# Power_Regulation.net
KiCad netlist of a schematic drawn in Altium Designer
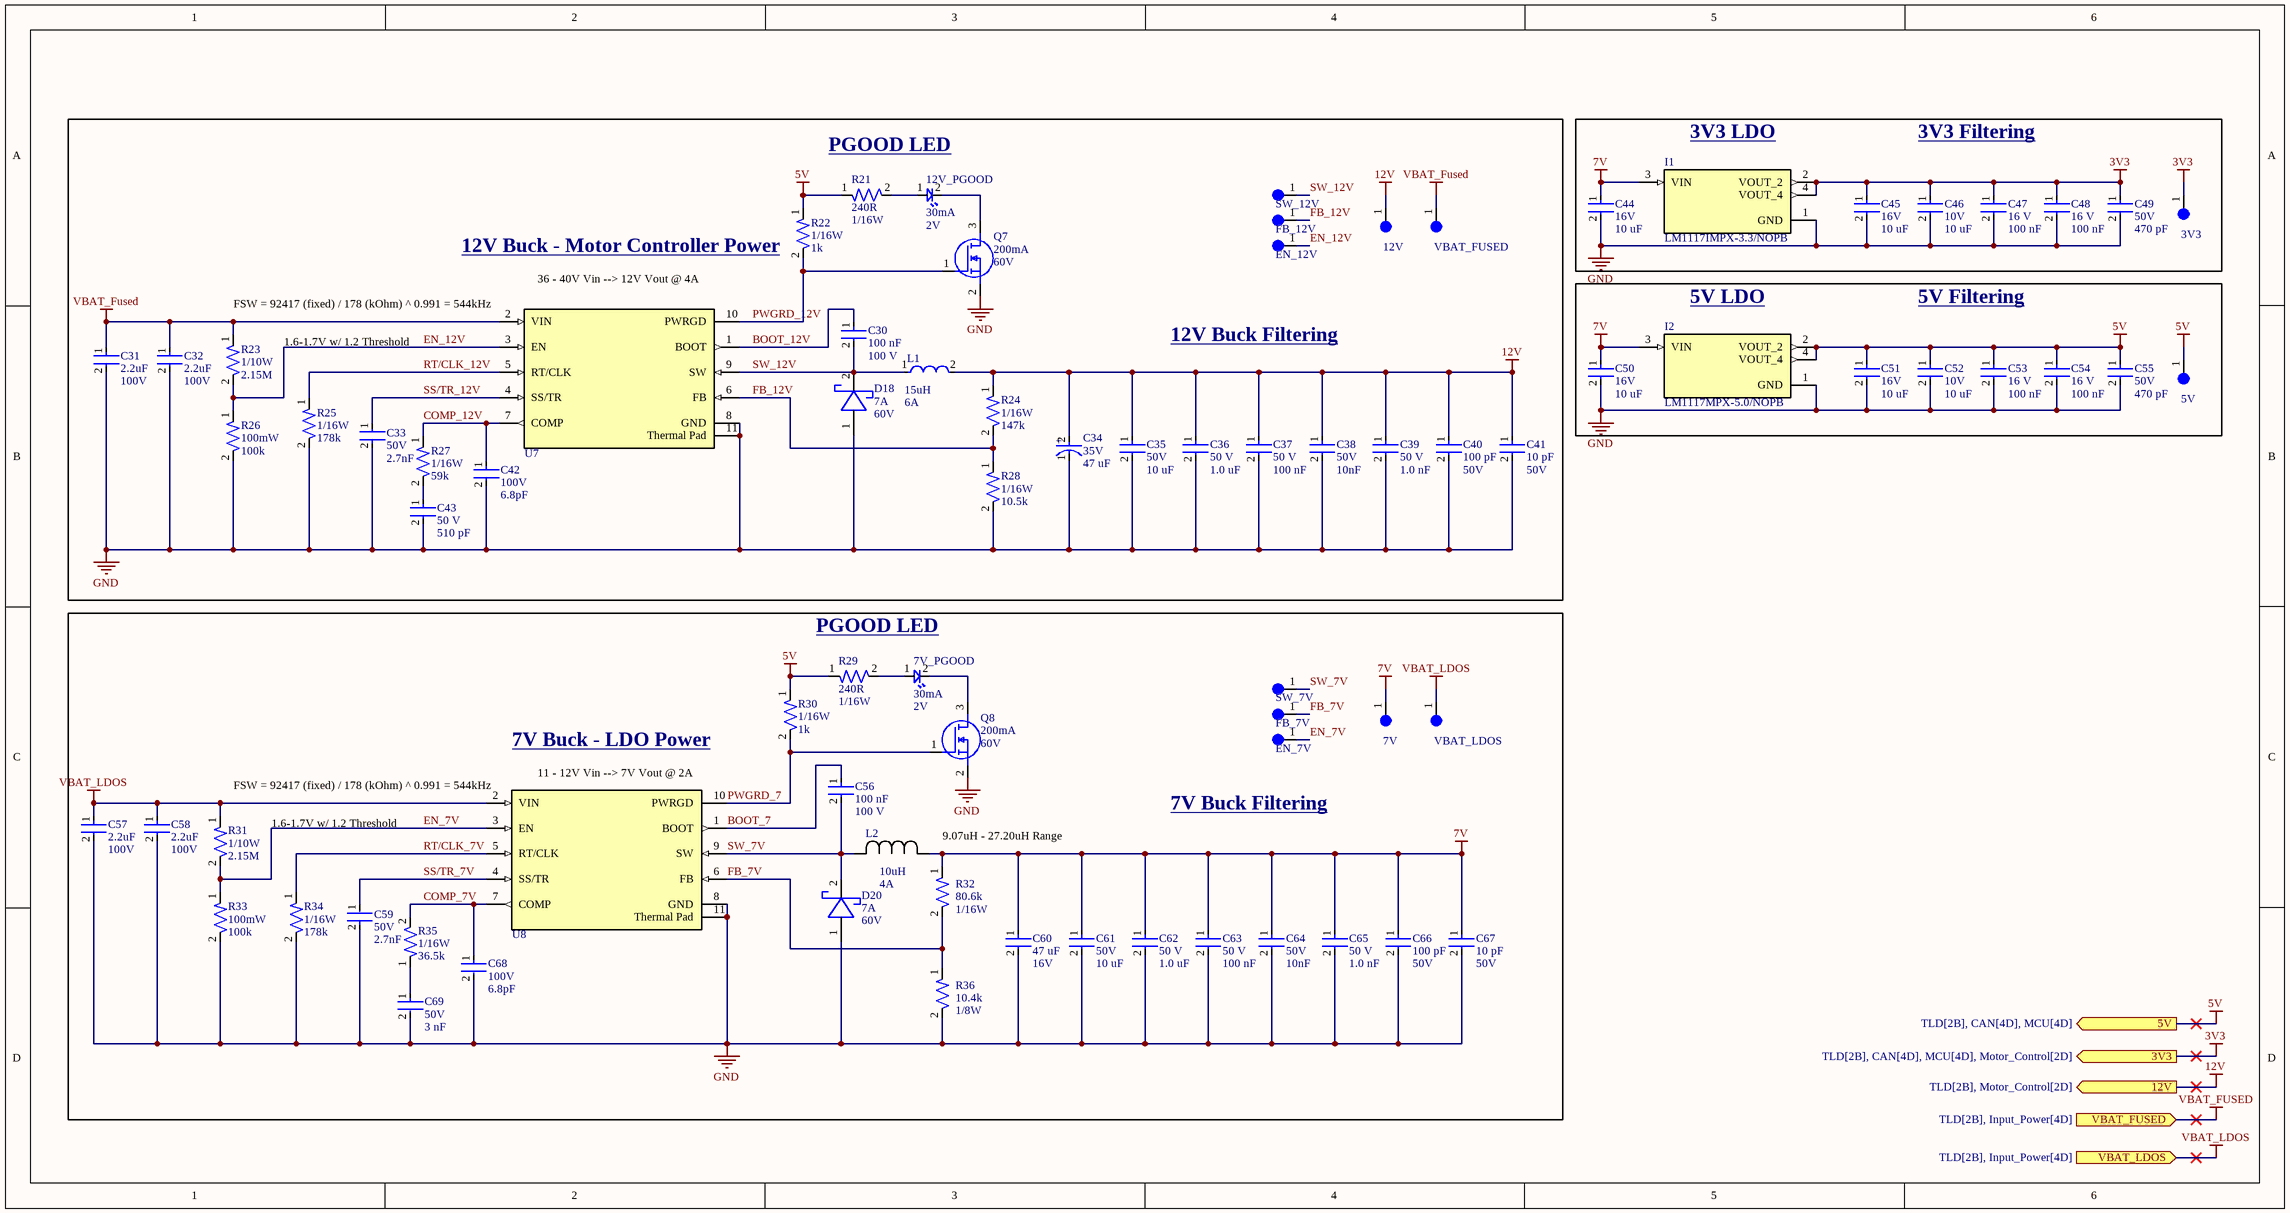
[diagram p0: Power_Regulation.SchDoc]

(export (version "E")
  (design (tool "Eeschema 10.0.6"))
  (components
    (comp (ref "3V3")
      (value "5003")
      (footprint "TEST-POINT-0001")
      (description "Oranange PC Test Point, Miniature Phoisphor Bronze Silver Plating Through Hole Mounting Type")
      (libsource (lib "*") (part "TEST-POINT-0001"))
    )
    (comp (ref "5V")
      (value "5003")
      (footprint "TEST-POINT-0001")
      (description "Oranange PC Test Point, Miniature Phoisphor Bronze Silver Plating Through Hole Mounting Type")
      (libsource (lib "*") (part "TEST-POINT-0001"))
    )
    (comp (ref "7V")
      (value "5003")
      (footprint "TEST-POINT-0001")
      (description "Oranange PC Test Point, Miniature Phoisphor Bronze Silver Plating Through Hole Mounting Type")
      (libsource (lib "*") (part "TEST-POINT-0001"))
    )
    (comp (ref "7V_PGOOD")
      (value "BL-HKC36G-AV-TRB")
      (footprint "LED-0603")
      (description "LED YELLOW CLEAR 0603 SMD")
      (fields (field (name "FORWARD CURRENT") "30mA") (field (name "FORWARD VOLTAGE") "2V"))
      (libsource (lib "JLC_25") (part "LED-0001"))
    )
    (comp (ref "12V")
      (value "5003")
      (footprint "TEST-POINT-0001")
      (description "Oranange PC Test Point, Miniature Phoisphor Bronze Silver Plating Through Hole Mounting Type")
      (libsource (lib "*") (part "TEST-POINT-0001"))
    )
    (comp (ref "12V_PGOOD")
      (value "BL-HKC36G-AV-TRB")
      (footprint "LED-0603")
      (description "LED YELLOW CLEAR 0603 SMD")
      (fields (field (name "FORWARD CURRENT") "30mA") (field (name "FORWARD VOLTAGE") "2V"))
      (libsource (lib "JLC_25") (part "LED-0001"))
    )
    (comp (ref "C30")
      (value "CC0603KRX7R0BB104")
      (footprint "CAP-0603")
      (description "CAP CER 0.1UF 100V X7R 0603")
      (fields (field (name "CAPACITANCE") "100 nF") (field (name "VOLTAGE") "100 V"))
      (libsource (lib "JLC_25") (part "CAP-100N-0001"))
    )
    (comp (ref "C31")
      (value "CC1206KKX7R0BB225")
      (footprint "CAP-1206")
      (description "CAP CER 2.2UF 100V X7R 1206")
      (fields (field (name "CAPACITANCE") "2.2uF") (field (name "VOLTAGE") "100V"))
      (libsource (lib "JLC_25") (part "CAP-2.2U-0001"))
    )
    (comp (ref "C32")
      (value "CC1206KKX7R0BB225")
      (footprint "CAP-1206")
      (description "CAP CER 2.2UF 100V X7R 1206")
      (fields (field (name "CAPACITANCE") "2.2uF") (field (name "VOLTAGE") "100V"))
      (libsource (lib "JLC_25") (part "CAP-2.2U-0001"))
    )
    (comp (ref "C33")
      (value "GRM2165C1H272JA01D")
      (footprint "CAP-0805")
      (description "CAP CER 2700PF 50V C0G/NP0 0805")
      (fields (field (name "VOLTAGE") "50V") (field (name "CAPACITANCE") "2.7nF"))
      (libsource (lib "JLC_25") (part "CAP-2.7N-0001"))
    )
    (comp (ref "C34")
      (value "EEH-ZC1V470P")
      (footprint "CAP-Radial-SMD")
      (description "CAP ALUM HYBRID 47UF 20% 35V SMD")
      (fields (field (name "VOLTAGE") "35V") (field (name "CAPACITANCE") "47 uF"))
      (libsource (lib "JLC_25") (part "CAP-47U-0002"))
    )
    (comp (ref "C35")
      (value "CL32B106KBJNNNE")
      (footprint "CAP-1210")
      (description "CAP CER 10UF 50V X7R 1210")
      (fields (field (name "VOLTAGE") "50V") (field (name "CAPACITANCE") "10 uF"))
      (libsource (lib "JLC_25") (part "CAP-10U-0002"))
    )
    (comp (ref "C36")
      (value "CC0805KKX7R9BB105")
      (footprint "CAP-0805")
      (description "CAP CER 1UF 50V X7R 0805")
      (fields (field (name "VOLTAGE") "50 V") (field (name "CAPACITANCE") "1.0 uF"))
      (libsource (lib "JLC_25") (part "CAP-1U-0001"))
    )
    (comp (ref "C37")
      (value "CC0805KRX7R9BB104")
      (footprint "CAP-0805")
      (description "CAP CER 0.1UF 50V X7R 0805")
      (fields (field (name "VOLTAGE RATING") "50 V") (field (name "CAPACITANCE") "100 nF"))
      (libsource (lib "JLC_25") (part "CAP-0.1U-0002"))
    )
    (comp (ref "C38")
      (value "GRM2195C1H103JA01D")
      (footprint "CAP-0805")
      (description "CAP CER 10000PF 50V C0G/NP0 0805")
      (fields (field (name "VOLTAGE") "50V") (field (name "CAPACITANCE") "10nF"))
      (libsource (lib "JLC_25") (part "CAP-10N-0001"))
    )
    (comp (ref "C39")
      (value "CC0402KRX7R9BB102")
      (footprint "CAP-0402")
      (description "CAP CER 1000PF 50V X7R 0402")
      (fields (field (name "VOLTAGE") "50 V") (field (name "CAPACITANCE") "1.0 nF"))
      (libsource (lib "JLC_25") (part "CAP-1N-0001"))
    )
    (comp (ref "C40")
      (value "CC0402JRNPO9BN101")
      (footprint "CAP-0402")
      (description "CAP CER 100PF 50V C0G/NPO 0402")
      (fields (field (name "CAPACITANCE") "100 pF") (field (name "VOLTAGE") "50V"))
      (libsource (lib "JLC_25") (part "CAP-100P-0001"))
    )
    (comp (ref "C41")
      (value "CC0402JRNPO9BN100")
      (footprint "CAP-0402")
      (description "CAP CER 10PF 50V C0G/NPO 0402")
      (fields (field (name "CAPACITANCE") "10 pF") (field (name "VOLTAGE") "50V"))
      (libsource (lib "JLC_25") (part "CAP-10P-0001"))
    )
    (comp (ref "C42")
      (value "CC0603CRNPO0BN6R8")
      (footprint "CAP-0603")
      (description "CAP CER 6.8PF 100V C0G/NPO 0603")
      (fields (field (name "VOLTAGE") "100V") (field (name "CAPACITANCE") "6.8pF"))
      (libsource (lib "JLC_25") (part "CAP-6.8P-0001"))
    )
    (comp (ref "C43")
      (value "0402N511J500CT")
      (footprint "CAP-0402")
      (description "CAP CER 510PF 50V C0G/NP0 0402")
      (fields (field (name "VOLTAGE") "50 V") (field (name "CAPACITANCE") "510 pF"))
      (libsource (lib "JLC_25") (part "CAP-510P-0001"))
    )
    (comp (ref "C44")
      (value "293D106X9016A2TE3")
      (footprint "CAP-1206")
      (description "CAP TANT 10UF 10% 16V 1206")
      (fields (field (name "VOLTAGE") "16V") (field (name "CAPACITANCE") "10 uF"))
      (libsource (lib "JLC_25") (part "CAP-10U-0004"))
    )
    (comp (ref "C45")
      (value "293D106X9016A2TE3")
      (footprint "CAP-1206")
      (description "CAP TANT 10UF 10% 16V 1206")
      (fields (field (name "VOLTAGE") "16V") (field (name "CAPACITANCE") "10 uF"))
      (libsource (lib "JLC_25") (part "CAP-10U-0004"))
    )
    (comp (ref "C46")
      (value "CC0603KRX5R6BB106")
      (footprint "CAP-0603")
      (description "CAP CER 10UF 10V X5R 0603")
      (fields (field (name "VOLTAGE") "10V") (field (name "CAPACITANCE") "10 uF"))
      (libsource (lib "JLC_25") (part "CAP-10U-0001"))
    )
    (comp (ref "C47")
      (value "CC0402KRX7R7BB104")
      (footprint "CAP-0402")
      (description "CAP CER 0.1UF 16V X7R 0402")
      (fields (field (name "VOLTAGE RATING") "16 V") (field (name "CAPACITANCE") "100 nF"))
      (libsource (lib "JLC_25") (part "CAP-0.1U-0001"))
    )
    (comp (ref "C48")
      (value "CC0402KRX7R7BB104")
      (footprint "CAP-0402")
      (description "CAP CER 0.1UF 16V X7R 0402")
      (fields (field (name "VOLTAGE RATING") "16 V") (field (name "CAPACITANCE") "100 nF"))
      (libsource (lib "JLC_25") (part "CAP-0.1U-0001"))
    )
    (comp (ref "C49")
      (value "CC0805JRNPO9BN471")
      (footprint "CAP-0805")
      (description "CAP CER 470PF 50V C0G/NPO 0805")
      (fields (field (name "VOLTAGE") "50V") (field (name "CAPACITANCE") "470 pF"))
      (libsource (lib "JLC_25") (part "CAP-470P-0001"))
    )
    (comp (ref "C50")
      (value "293D106X9016A2TE3")
      (footprint "CAP-1206")
      (description "CAP TANT 10UF 10% 16V 1206")
      (fields (field (name "VOLTAGE") "16V") (field (name "CAPACITANCE") "10 uF"))
      (libsource (lib "JLC_25") (part "CAP-10U-0004"))
    )
    (comp (ref "C51")
      (value "293D106X9016A2TE3")
      (footprint "CAP-1206")
      (description "CAP TANT 10UF 10% 16V 1206")
      (fields (field (name "VOLTAGE") "16V") (field (name "CAPACITANCE") "10 uF"))
      (libsource (lib "JLC_25") (part "CAP-10U-0004"))
    )
    (comp (ref "C52")
      (value "CC0603KRX5R6BB106")
      (footprint "CAP-0603")
      (description "CAP CER 10UF 10V X5R 0603")
      (fields (field (name "VOLTAGE") "10V") (field (name "CAPACITANCE") "10 uF"))
      (libsource (lib "JLC_25") (part "CAP-10U-0001"))
    )
    (comp (ref "C53")
      (value "CC0402KRX7R7BB104")
      (footprint "CAP-0402")
      (description "CAP CER 0.1UF 16V X7R 0402")
      (fields (field (name "VOLTAGE RATING") "16 V") (field (name "CAPACITANCE") "100 nF"))
      (libsource (lib "JLC_25") (part "CAP-0.1U-0001"))
    )
    (comp (ref "C54")
      (value "CC0402KRX7R7BB104")
      (footprint "CAP-0402")
      (description "CAP CER 0.1UF 16V X7R 0402")
      (fields (field (name "VOLTAGE RATING") "16 V") (field (name "CAPACITANCE") "100 nF"))
      (libsource (lib "JLC_25") (part "CAP-0.1U-0001"))
    )
    (comp (ref "C55")
      (value "CC0805JRNPO9BN471")
      (footprint "CAP-0805")
      (description "CAP CER 470PF 50V C0G/NPO 0805")
      (fields (field (name "VOLTAGE") "50V") (field (name "CAPACITANCE") "470 pF"))
      (libsource (lib "JLC_25") (part "CAP-470P-0001"))
    )
    (comp (ref "C56")
      (value "CC0603KRX7R0BB104")
      (footprint "CAP-0603")
      (description "CAP CER 0.1UF 100V X7R 0603")
      (fields (field (name "CAPACITANCE") "100 nF") (field (name "VOLTAGE") "100 V"))
      (libsource (lib "JLC_25") (part "CAP-100N-0001"))
    )
    (comp (ref "C57")
      (value "CC1206KKX7R0BB225")
      (footprint "CAP-1206")
      (description "CAP CER 2.2UF 100V X7R 1206")
      (fields (field (name "CAPACITANCE") "2.2uF") (field (name "VOLTAGE") "100V"))
      (libsource (lib "JLC_25") (part "CAP-2.2U-0001"))
    )
    (comp (ref "C58")
      (value "CC1206KKX7R0BB225")
      (footprint "CAP-1206")
      (description "CAP CER 2.2UF 100V X7R 1206")
      (fields (field (name "CAPACITANCE") "2.2uF") (field (name "VOLTAGE") "100V"))
      (libsource (lib "JLC_25") (part "CAP-2.2U-0001"))
    )
    (comp (ref "C59")
      (value "GRM2165C1H272JA01D")
      (footprint "CAP-0805")
      (description "CAP CER 2700PF 50V C0G/NP0 0805")
      (fields (field (name "VOLTAGE") "50V") (field (name "CAPACITANCE") "2.7nF"))
      (libsource (lib "JLC_25") (part "CAP-2.7N-0001"))
    )
    (comp (ref "C60")
      (value "C3225X7R1N106K250AC")
      (footprint "CAP-1210")
      (description "CAP CER 47UF 16V X5R 1210")
      (fields (field (name "CAPACITANCE") "47 uF") (field (name "VOLTAGE") "16V"))
      (libsource (lib "JLC_25") (part "CAP-47U-0003"))
    )
    (comp (ref "C61")
      (value "CL32B106KBJNNNE")
      (footprint "CAP-1210")
      (description "CAP CER 10UF 50V X7R 1210")
      (fields (field (name "VOLTAGE") "50V") (field (name "CAPACITANCE") "10 uF"))
      (libsource (lib "JLC_25") (part "CAP-10U-0002"))
    )
    (comp (ref "C62")
      (value "CC0805KKX7R9BB105")
      (footprint "CAP-0805")
      (description "CAP CER 1UF 50V X7R 0805")
      (fields (field (name "VOLTAGE") "50 V") (field (name "CAPACITANCE") "1.0 uF"))
      (libsource (lib "JLC_25") (part "CAP-1U-0001"))
    )
    (comp (ref "C63")
      (value "CC0805KRX7R9BB104")
      (footprint "CAP-0805")
      (description "CAP CER 0.1UF 50V X7R 0805")
      (fields (field (name "VOLTAGE RATING") "50 V") (field (name "CAPACITANCE") "100 nF"))
      (libsource (lib "JLC_25") (part "CAP-0.1U-0002"))
    )
    (comp (ref "C64")
      (value "GRM2195C1H103JA01D")
      (footprint "CAP-0805")
      (description "CAP CER 10000PF 50V C0G/NP0 0805")
      (fields (field (name "VOLTAGE") "50V") (field (name "CAPACITANCE") "10nF"))
      (libsource (lib "JLC_25") (part "CAP-10N-0001"))
    )
    (comp (ref "C65")
      (value "CC0402KRX7R9BB102")
      (footprint "CAP-0402")
      (description "CAP CER 1000PF 50V X7R 0402")
      (fields (field (name "VOLTAGE") "50 V") (field (name "CAPACITANCE") "1.0 nF"))
      (libsource (lib "JLC_25") (part "CAP-1N-0001"))
    )
    (comp (ref "C66")
      (value "CC0402JRNPO9BN101")
      (footprint "CAP-0402")
      (description "CAP CER 100PF 50V C0G/NPO 0402")
      (fields (field (name "CAPACITANCE") "100 pF") (field (name "VOLTAGE") "50V"))
      (libsource (lib "JLC_25") (part "CAP-100P-0001"))
    )
    (comp (ref "C67")
      (value "CC0402JRNPO9BN100")
      (footprint "CAP-0402")
      (description "CAP CER 10PF 50V C0G/NPO 0402")
      (fields (field (name "CAPACITANCE") "10 pF") (field (name "VOLTAGE") "50V"))
      (libsource (lib "JLC_25") (part "CAP-10P-0001"))
    )
    (comp (ref "C68")
      (value "CC0603CRNPO0BN6R8")
      (footprint "CAP-0603")
      (description "CAP CER 6.8PF 100V C0G/NPO 0603")
      (fields (field (name "VOLTAGE") "100V") (field (name "CAPACITANCE") "6.8pF"))
      (libsource (lib "JLC_25") (part "CAP-6.8P-0001"))
    )
    (comp (ref "C69")
      (value "GRM1885C1H302JA01D")
      (footprint "CAP-0603")
      (description "3000 pF ±5% 50V Ceramic Capacitor C0G, NP0 0603 (1608 Metric)")
      (fields (field (name "VOLTAGE") "50V") (field (name "CAPACITANCE") "3 nF"))
      (libsource (lib "JLC_25") (part "CAP-3N-0001"))
    )
    (comp (ref "D18")
      (value "PDS760-13")
      (footprint "DO-POWERDI5")
      (description "DIODE SCHOTTKY 60V 7A POWERDI5")
      (fields (field (name "FORWARD CURRENT") "7A") (field (name "REVERSE VOLTAGE (DC)") "60V"))
      (libsource (lib "JLC_25") (part "DIO-SCHOTTKY-0001"))
    )
    (comp (ref "D20")
      (value "PDS760-13")
      (footprint "DO-POWERDI5")
      (description "DIODE SCHOTTKY 60V 7A POWERDI5")
      (fields (field (name "FORWARD CURRENT") "7A") (field (name "REVERSE VOLTAGE (DC)") "60V"))
      (libsource (lib "JLC_25") (part "DIO-SCHOTTKY-0001"))
    )
    (comp (ref "EN_7V")
      (value "5003")
      (footprint "TEST-POINT-0001")
      (description "Oranange PC Test Point, Miniature Phoisphor Bronze Silver Plating Through Hole Mounting Type")
      (libsource (lib "*") (part "TEST-POINT-0001"))
    )
    (comp (ref "EN_12V")
      (value "5003")
      (footprint "TEST-POINT-0001")
      (description "Oranange PC Test Point, Miniature Phoisphor Bronze Silver Plating Through Hole Mounting Type")
      (libsource (lib "*") (part "TEST-POINT-0001"))
    )
    (comp (ref "FB_7V")
      (value "5003")
      (footprint "TEST-POINT-0001")
      (description "Oranange PC Test Point, Miniature Phoisphor Bronze Silver Plating Through Hole Mounting Type")
      (libsource (lib "*") (part "TEST-POINT-0001"))
    )
    (comp (ref "FB_12V")
      (value "5003")
      (footprint "TEST-POINT-0001")
      (description "Oranange PC Test Point, Miniature Phoisphor Bronze Silver Plating Through Hole Mounting Type")
      (libsource (lib "*") (part "TEST-POINT-0001"))
    )
    (comp (ref "I1")
      (value "LM1117IMPX-3.3/NOPB")
      (footprint "IC-SOT-223-4")
      (description "IC REG LIN 3.3V 800MA SOT223-4")
      (libsource (lib "JLC_25") (part "IC_LDO_3V3_0001"))
    )
    (comp (ref "I2")
      (value "LM1117MPX-5.0/NOPB")
      (footprint "IC-SOT-223-4")
      (description "IC REG LINEAR 5V 800MA SOT223-4")
      (libsource (lib "JLC_25") (part "IC_LDO_5V_0001"))
    )
    (comp (ref "L1")
      (value "CSAD1010-150M")
      (footprint "IND-15U-0002")
      (description "SMD MOLDING POWER CHOKE")
      (fields (field (name "INDUCTANCE") "15uH") (field (name "CURRENT RATING") "6A"))
      (libsource (lib "JLC_25") (part "IND-15U-0002-NoJLC"))
    )
    (comp (ref "L2")
      (value "IHLP2525CZER100M11")
      (footprint "IND_IHLP_2525_CZ_VIS")
      (description "IHLP-2525CZ-11 10 20% ER E3")
      (fields
        (field (name "CURRENT") "4A")
        (field (name "INDUCTANCE") "10uH")
        (field (name "COPYRIGHT") "Copyright (C) 2025 Ultra Librarian. All rights reserved.")
      )
      (libsource (lib "JLC_25") (part "IND-10U-0002"))
    )
    (comp (ref "Q7")
      (value "T2N7002AK,LM")
      (footprint "IC-SOT23-3")
      (description "MOSFET N-CH 60V 200MA SOT23")
      (fields (field (name "CONTINUOUS CURRENT") "200mA") (field (name "VOLTAGE") "60V"))
      (libsource (lib "JLC_25") (part "NMOS-200MA-0001"))
    )
    (comp (ref "Q8")
      (value "T2N7002AK,LM")
      (footprint "IC-SOT23-3")
      (description "MOSFET N-CH 60V 200MA SOT23")
      (fields (field (name "CONTINUOUS CURRENT") "200mA") (field (name "VOLTAGE") "60V"))
      (libsource (lib "JLC_25") (part "NMOS-200MA-0001"))
    )
    (comp (ref "R21")
      (value "RC0402FR-07240RL")
      (footprint "RES-0402")
      (description "240R 0.063W 1% 0402 (1005 Metric)  SMD")
      (fields
        (field (name "TOLERANCE") "1%")
        (field (name "RESISTANCE") "240R")
        (field (name "POWER") "1/16W")
      )
      (libsource (lib "JLC_25") (part "RES-240-0001"))
    )
    (comp (ref "R22")
      (value "RC0402FR-071KL")
      (footprint "RES-0402")
      (description "RES 1K OHM 1% 1/16W 0402")
      (fields (field (name "TOLERANCE") "1%") (field (name "POWER") "1/16W") (field (name "RESISTANCE") "1k"))
      (libsource (lib "JLC_25") (part "RES-1k-0001"))
    )
    (comp (ref "R23")
      (value "RC0603FR-072M15L")
      (footprint "RES-0603")
      (description "RES SMD 2.15M OHM 1% 1/10W 0603")
      (fields
        (field (name "TOLERANCE") "1%")
        (field (name "POWER") "1/10W")
        (field (name "RESISTANCE") "2.15M")
      )
      (libsource (lib "JLC_25") (part "RES-2.15M-0001"))
    )
    (comp (ref "R24")
      (value "RC0402FR-07147KL")
      (footprint "RES-0402")
      (description "RES 147K OHM 1% 1/16W 0402")
      (fields
        (field (name "TOLERANCE") "1%")
        (field (name "POWER") "1/16W")
        (field (name "RESISTANCE") "147k")
      )
      (libsource (lib "JLC_25") (part "RES-147k-0001"))
    )
    (comp (ref "R25")
      (value "RTT021783FTH")
      (footprint "RES-0402")
      (description "62.5mW Thick Film Resistors 50V ±100ppm/℃ ±1% 178kΩ 0402 Chip Resistor - Surface Mount ROHS")
      (fields
        (field (name "TOLERANCE") "1%")
        (field (name "POWER") "1/16W")
        (field (name "RESISTANCE") "178k")
      )
      (libsource (lib "JLC_25") (part "RES-178k-0001"))
    )
    (comp (ref "R26")
      (value "RC0603FR-07100KL")
      (footprint "RES-0603")
      (description "RES SMD 100K OHM 1% 1/10W 0603")
      (fields
        (field (name "TOLERANCE") "1%")
        (field (name "POWER") "100mW")
        (field (name "RESISTANCE") "100k")
      )
      (libsource (lib "JLC_25") (part "RES-100k-0001"))
    )
    (comp (ref "R27")
      (value "RC0402FR-0759KL")
      (footprint "RES-0402")
      (description "RES 59K OHM 1% 1/16W 0402")
      (fields
        (field (name "TOLERANCE") "1%")
        (field (name "POWER") "1/16W")
        (field (name "RESISTANCE") "59k")
      )
      (libsource (lib "JLC_25") (part "RES-59k-0001"))
    )
    (comp (ref "R28")
      (value "RC0402FR-0710K5L")
      (footprint "RES-0402")
      (description "RES 10.5K OHM 1% 1/16W 0402")
      (fields
        (field (name "TOLERANCE") "1%")
        (field (name "POWER") "1/16W")
        (field (name "RESISTANCE") "10.5k")
      )
      (libsource (lib "JLC_25") (part "RES-10.5k-0001"))
    )
    (comp (ref "R29")
      (value "RC0402FR-07240RL")
      (footprint "RES-0402")
      (description "240R 0.063W 1% 0402 (1005 Metric)  SMD")
      (fields
        (field (name "TOLERANCE") "1%")
        (field (name "RESISTANCE") "240R")
        (field (name "POWER") "1/16W")
      )
      (libsource (lib "JLC_25") (part "RES-240-0001"))
    )
    (comp (ref "R30")
      (value "RC0402FR-071KL")
      (footprint "RES-0402")
      (description "RES 1K OHM 1% 1/16W 0402")
      (fields (field (name "TOLERANCE") "1%") (field (name "POWER") "1/16W") (field (name "RESISTANCE") "1k"))
      (libsource (lib "JLC_25") (part "RES-1k-0001"))
    )
    (comp (ref "R31")
      (value "RC0603FR-072M15L")
      (footprint "RES-0603")
      (description "RES SMD 2.15M OHM 1% 1/10W 0603")
      (fields
        (field (name "TOLERANCE") "1%")
        (field (name "POWER") "1/10W")
        (field (name "RESISTANCE") "2.15M")
      )
      (libsource (lib "JLC_25") (part "RES-2.15M-0001"))
    )
    (comp (ref "R32")
      (value "RC0402FR-0780K6L")
      (footprint "RES-0402")
      (description "80.6 kOhms ±1% 0.063W, 1/16W Chip Resistor 0402 (1005 Metric) Moisture Resistant Thick Film")
      (fields
        (field (name "TOLERANCE") "1%")
        (field (name "RESISTANCE") "80.6k")
        (field (name "POWER") "1/16W")
      )
      (libsource (lib "JLC_25") (part "RES-80.6k-0001"))
    )
    (comp (ref "R33")
      (value "RC0603FR-07100KL")
      (footprint "RES-0603")
      (description "RES SMD 100K OHM 1% 1/10W 0603")
      (fields
        (field (name "TOLERANCE") "1%")
        (field (name "POWER") "100mW")
        (field (name "RESISTANCE") "100k")
      )
      (libsource (lib "JLC_25") (part "RES-100k-0001"))
    )
    (comp (ref "R34")
      (value "RTT021783FTH")
      (footprint "RES-0402")
      (description "62.5mW Thick Film Resistors 50V ±100ppm/℃ ±1% 178kΩ 0402 Chip Resistor - Surface Mount ROHS")
      (fields
        (field (name "TOLERANCE") "1%")
        (field (name "POWER") "1/16W")
        (field (name "RESISTANCE") "178k")
      )
      (libsource (lib "JLC_25") (part "RES-178k-0001"))
    )
    (comp (ref "R35")
      (value "RC0402FR-0736K5L")
      (footprint "RES-0402")
      (description "36.5 kOhms ±1% 0.063W, 1/16W Chip Resistor 0402 (1005 Metric) Moisture Resistant Thick Film")
      (fields (field (name "POWER") "1/16W") (field (name "RESISTANCE") "36.5k"))
      (libsource (lib "JLC_25") (part "RES-36.5k-0001"))
    )
    (comp (ref "R36")
      (value "RT0805BRD0710K4L")
      (footprint "RES-0805")
      (description "10.4 kOhms ±0.1% 0.125W, 1/8W Chip Resistor 0805 (2012 Metric) Thin Film")
      (fields
        (field (name "TOLERANCE") "1%")
        (field (name "POWER") "1/8W")
        (field (name "RESISTANCE") "10.4k")
      )
      (libsource (lib "JLC_25") (part "RES-10.4k-0001"))
    )
    (comp (ref "SW_7V")
      (value "5003")
      (footprint "TEST-POINT-0001")
      (description "Oranange PC Test Point, Miniature Phoisphor Bronze Silver Plating Through Hole Mounting Type")
      (libsource (lib "*") (part "TEST-POINT-0001"))
    )
    (comp (ref "SW_12V")
      (value "5003")
      (footprint "TEST-POINT-0001")
      (description "Oranange PC Test Point, Miniature Phoisphor Bronze Silver Plating Through Hole Mounting Type")
      (libsource (lib "*") (part "TEST-POINT-0001"))
    )
    (comp (ref "U7")
      (value "TPS54561DPRR")
      (footprint "IC-10WSON")
      (description "IC REG BUCK ADJ 5A 10WSON")
      (libsource (lib "JLC_25") (part "IC-BUCK-0001"))
    )
    (comp (ref "U8")
      (value "TPS54561DPRR")
      (footprint "IC-10WSON")
      (description "IC REG BUCK ADJ 5A 10WSON")
      (libsource (lib "JLC_25") (part "IC-BUCK-0001"))
    )
    (comp (ref "VBAT_FUSED")
      (value "5003")
      (footprint "TEST-POINT-0001")
      (description "Oranange PC Test Point, Miniature Phoisphor Bronze Silver Plating Through Hole Mounting Type")
      (libsource (lib "*") (part "TEST-POINT-0001"))
    )
    (comp (ref "VBAT_LDOS")
      (value "5003")
      (footprint "TEST-POINT-0001")
      (description "Oranange PC Test Point, Miniature Phoisphor Bronze Silver Plating Through Hole Mounting Type")
      (libsource (lib "*") (part "TEST-POINT-0001"))
    )
  )
  (nets
    (net (code "1") (name "/BOOT_7") (class "Default")
      (node (ref "C56") (pin "1") (pinfunction "1_1") (pintype "passive"))
      (node (ref "U8") (pin "1") (pinfunction "BOOT_1") (pintype "output"))
    )
    (net (code "2") (name "/BOOT_12V") (class "Default")
      (node (ref "C30") (pin "1") (pinfunction "1_1") (pintype "passive"))
      (node (ref "U7") (pin "1") (pinfunction "BOOT_1") (pintype "output"))
    )
    (net (code "3") (name "/COMP_7V") (class "Default")
      (node (ref "C68") (pin "1") (pinfunction "1_1") (pintype "passive"))
      (node (ref "R35") (pin "2") (pinfunction "2_2") (pintype "passive"))
      (node (ref "U8") (pin "7") (pinfunction "COMP_7") (pintype "output"))
    )
    (net (code "4") (name "/COMP_12V") (class "Default")
      (node (ref "C42") (pin "1") (pinfunction "1_1") (pintype "passive"))
      (node (ref "R27") (pin "1") (pinfunction "1_1") (pintype "passive"))
      (node (ref "U7") (pin "7") (pinfunction "COMP_7") (pintype "output"))
    )
    (net (code "5") (name "/EN_7V") (class "Default")
      (node (ref "EN_7V") (pin "1") (pinfunction "0_1") (pintype "passive"))
      (node (ref "R31") (pin "2") (pinfunction "2_2") (pintype "passive"))
      (node (ref "R33") (pin "1") (pinfunction "1_1") (pintype "passive"))
      (node (ref "U8") (pin "3") (pinfunction "EN_3") (pintype "input"))
    )
    (net (code "6") (name "/EN_12V") (class "Default")
      (node (ref "EN_12V") (pin "1") (pinfunction "0_1") (pintype "passive"))
      (node (ref "R23") (pin "2") (pinfunction "2_2") (pintype "passive"))
      (node (ref "R26") (pin "1") (pinfunction "1_1") (pintype "passive"))
      (node (ref "U7") (pin "3") (pinfunction "EN_3") (pintype "input"))
    )
    (net (code "7") (name "/FB_7V") (class "Default")
      (node (ref "FB_7V") (pin "1") (pinfunction "0_1") (pintype "passive"))
      (node (ref "R32") (pin "2") (pinfunction "2_2") (pintype "passive"))
      (node (ref "R36") (pin "1") (pinfunction "1_1") (pintype "passive"))
      (node (ref "U8") (pin "6") (pinfunction "FB_6") (pintype "input"))
    )
    (net (code "8") (name "/FB_12V") (class "Default")
      (node (ref "FB_12V") (pin "1") (pinfunction "0_1") (pintype "passive"))
      (node (ref "R24") (pin "2") (pinfunction "2_2") (pintype "passive"))
      (node (ref "R28") (pin "1") (pinfunction "1_1") (pintype "passive"))
      (node (ref "U7") (pin "6") (pinfunction "FB_6") (pintype "input"))
    )
    (net (code "9") (name "/PWGRD_7") (class "Default")
      (node (ref "Q8") (pin "1") (pinfunction "G_1") (pintype "passive"))
      (node (ref "R30") (pin "2") (pinfunction "2_2") (pintype "passive"))
      (node (ref "U8") (pin "10") (pinfunction "PWRGD_10") (pintype "open_collector"))
    )
    (net (code "10") (name "/PWGRD_12V") (class "Default")
      (node (ref "Q7") (pin "1") (pinfunction "G_1") (pintype "passive"))
      (node (ref "R22") (pin "2") (pinfunction "2_2") (pintype "passive"))
      (node (ref "U7") (pin "10") (pinfunction "PWRGD_10") (pintype "open_collector"))
    )
    (net (code "11") (name "/RT{slash}CLK_7V") (class "Default")
      (node (ref "R34") (pin "1") (pinfunction "1_1") (pintype "passive"))
      (node (ref "U8") (pin "5") (pinfunction "RT/CLK_5") (pintype "input"))
    )
    (net (code "12") (name "/RT{slash}CLK_12V") (class "Default")
      (node (ref "R25") (pin "1") (pinfunction "1_1") (pintype "passive"))
      (node (ref "U7") (pin "5") (pinfunction "RT/CLK_5") (pintype "input"))
    )
    (net (code "13") (name "/SS{slash}TR_7V") (class "Default")
      (node (ref "C59") (pin "1") (pinfunction "1_1") (pintype "passive"))
      (node (ref "U8") (pin "4") (pinfunction "SS/TR_4") (pintype "input"))
    )
    (net (code "14") (name "/SS{slash}TR_12V") (class "Default")
      (node (ref "C33") (pin "1") (pinfunction "1_1") (pintype "passive"))
      (node (ref "U7") (pin "4") (pinfunction "SS/TR_4") (pintype "input"))
    )
    (net (code "15") (name "/SW_7V") (class "Default")
      (node (ref "C56") (pin "2") (pinfunction "2_2") (pintype "passive"))
      (node (ref "D20") (pin "2") (pinfunction "ANODE_2") (pintype "passive"))
      (node (ref "L2") (pin "2") (pinfunction "2_2") (pintype "passive"))
      (node (ref "SW_7V") (pin "1") (pinfunction "0_1") (pintype "passive"))
      (node (ref "U8") (pin "9") (pinfunction "SW_9") (pintype "input"))
    )
    (net (code "16") (name "/SW_12V") (class "Default")
      (node (ref "C30") (pin "2") (pinfunction "2_2") (pintype "passive"))
      (node (ref "D18") (pin "2") (pinfunction "ANODE_2") (pintype "passive"))
      (node (ref "L1") (pin "1") (pinfunction "1_1") (pintype "passive"))
      (node (ref "SW_12V") (pin "1") (pinfunction "0_1") (pintype "passive"))
      (node (ref "U7") (pin "9") (pinfunction "SW_9") (pintype "input"))
    )
    (net (code "17") (name "3V3") (class "Default")
      (node (ref "3V3") (pin "1") (pinfunction "0_1") (pintype "passive"))
      (node (ref "C45") (pin "1") (pinfunction "1_1") (pintype "passive"))
      (node (ref "C46") (pin "1") (pinfunction "1_1") (pintype "passive"))
      (node (ref "C47") (pin "1") (pinfunction "1_1") (pintype "passive"))
      (node (ref "C48") (pin "1") (pinfunction "1_1") (pintype "passive"))
      (node (ref "C49") (pin "1") (pinfunction "1_1") (pintype "passive"))
      (node (ref "I1") (pin "2") (pinfunction "VOUT_2_2") (pintype "output"))
      (node (ref "I1") (pin "4") (pinfunction "VOUT_4_4") (pintype "output"))
    )
    (net (code "18") (name "5V") (class "Default")
      (node (ref "5V") (pin "1") (pinfunction "0_1") (pintype "passive"))
      (node (ref "C51") (pin "1") (pinfunction "1_1") (pintype "passive"))
      (node (ref "C52") (pin "1") (pinfunction "1_1") (pintype "passive"))
      (node (ref "C53") (pin "1") (pinfunction "1_1") (pintype "passive"))
      (node (ref "C54") (pin "1") (pinfunction "1_1") (pintype "passive"))
      (node (ref "C55") (pin "1") (pinfunction "1_1") (pintype "passive"))
      (node (ref "I2") (pin "2") (pinfunction "VOUT_2_2") (pintype "output"))
      (node (ref "I2") (pin "4") (pinfunction "VOUT_4_4") (pintype "output"))
      (node (ref "R21") (pin "1") (pinfunction "1_1") (pintype "passive"))
      (node (ref "R22") (pin "1") (pinfunction "1_1") (pintype "passive"))
      (node (ref "R29") (pin "1") (pinfunction "1_1") (pintype "passive"))
      (node (ref "R30") (pin "1") (pinfunction "1_1") (pintype "passive"))
    )
    (net (code "19") (name "7V") (class "Default")
      (node (ref "7V") (pin "1") (pinfunction "0_1") (pintype "passive"))
      (node (ref "C44") (pin "1") (pinfunction "1_1") (pintype "passive"))
      (node (ref "C50") (pin "1") (pinfunction "1_1") (pintype "passive"))
      (node (ref "C60") (pin "1") (pinfunction "1_1") (pintype "passive"))
      (node (ref "C61") (pin "1") (pinfunction "1_1") (pintype "passive"))
      (node (ref "C62") (pin "1") (pinfunction "1_1") (pintype "passive"))
      (node (ref "C63") (pin "1") (pinfunction "1_1") (pintype "passive"))
      (node (ref "C64") (pin "1") (pinfunction "1_1") (pintype "passive"))
      (node (ref "C65") (pin "1") (pinfunction "1_1") (pintype "passive"))
      (node (ref "C66") (pin "1") (pinfunction "1_1") (pintype "passive"))
      (node (ref "C67") (pin "1") (pinfunction "1_1") (pintype "passive"))
      (node (ref "I1") (pin "3") (pinfunction "VIN_3") (pintype "input"))
      (node (ref "I2") (pin "3") (pinfunction "VIN_3") (pintype "input"))
      (node (ref "L2") (pin "1") (pinfunction "1_1") (pintype "passive"))
      (node (ref "R32") (pin "1") (pinfunction "1_1") (pintype "passive"))
    )
    (net (code "20") (name "12V") (class "Default")
      (node (ref "12V") (pin "1") (pinfunction "0_1") (pintype "passive"))
      (node (ref "C34") (pin "2") (pinfunction "A_2") (pintype "passive"))
      (node (ref "C35") (pin "1") (pinfunction "1_1") (pintype "passive"))
      (node (ref "C36") (pin "1") (pinfunction "1_1") (pintype "passive"))
      (node (ref "C37") (pin "1") (pinfunction "1_1") (pintype "passive"))
      (node (ref "C38") (pin "1") (pinfunction "1_1") (pintype "passive"))
      (node (ref "C39") (pin "1") (pinfunction "1_1") (pintype "passive"))
      (node (ref "C40") (pin "1") (pinfunction "1_1") (pintype "passive"))
      (node (ref "C41") (pin "1") (pinfunction "1_1") (pintype "passive"))
      (node (ref "L1") (pin "2") (pinfunction "2_2") (pintype "passive"))
      (node (ref "R24") (pin "1") (pinfunction "1_1") (pintype "passive"))
    )
    (net (code "21") (name "GND") (class "Default")
      (node (ref "C31") (pin "2") (pinfunction "2_2") (pintype "passive"))
      (node (ref "C32") (pin "2") (pinfunction "2_2") (pintype "passive"))
      (node (ref "C33") (pin "2") (pinfunction "2_2") (pintype "passive"))
      (node (ref "C34") (pin "1") (pinfunction "C_1") (pintype "passive"))
      (node (ref "C35") (pin "2") (pinfunction "2_2") (pintype "passive"))
      (node (ref "C36") (pin "2") (pinfunction "2_2") (pintype "passive"))
      (node (ref "C37") (pin "2") (pinfunction "2_2") (pintype "passive"))
      (node (ref "C38") (pin "2") (pinfunction "2_2") (pintype "passive"))
      (node (ref "C39") (pin "2") (pinfunction "2_2") (pintype "passive"))
      (node (ref "C40") (pin "2") (pinfunction "2_2") (pintype "passive"))
      (node (ref "C41") (pin "2") (pinfunction "2_2") (pintype "passive"))
      (node (ref "C42") (pin "2") (pinfunction "2_2") (pintype "passive"))
      (node (ref "C43") (pin "2") (pinfunction "2_2") (pintype "passive"))
      (node (ref "C44") (pin "2") (pinfunction "2_2") (pintype "passive"))
      (node (ref "C45") (pin "2") (pinfunction "2_2") (pintype "passive"))
      (node (ref "C46") (pin "2") (pinfunction "2_2") (pintype "passive"))
      (node (ref "C47") (pin "2") (pinfunction "2_2") (pintype "passive"))
      (node (ref "C48") (pin "2") (pinfunction "2_2") (pintype "passive"))
      (node (ref "C49") (pin "2") (pinfunction "2_2") (pintype "passive"))
      (node (ref "C50") (pin "2") (pinfunction "2_2") (pintype "passive"))
      (node (ref "C51") (pin "2") (pinfunction "2_2") (pintype "passive"))
      (node (ref "C52") (pin "2") (pinfunction "2_2") (pintype "passive"))
      (node (ref "C53") (pin "2") (pinfunction "2_2") (pintype "passive"))
      (node (ref "C54") (pin "2") (pinfunction "2_2") (pintype "passive"))
      (node (ref "C55") (pin "2") (pinfunction "2_2") (pintype "passive"))
      (node (ref "C57") (pin "2") (pinfunction "2_2") (pintype "passive"))
      (node (ref "C58") (pin "2") (pinfunction "2_2") (pintype "passive"))
      (node (ref "C59") (pin "2") (pinfunction "2_2") (pintype "passive"))
      (node (ref "C60") (pin "2") (pinfunction "2_2") (pintype "passive"))
      (node (ref "C61") (pin "2") (pinfunction "2_2") (pintype "passive"))
      (node (ref "C62") (pin "2") (pinfunction "2_2") (pintype "passive"))
      (node (ref "C63") (pin "2") (pinfunction "2_2") (pintype "passive"))
      (node (ref "C64") (pin "2") (pinfunction "2_2") (pintype "passive"))
      (node (ref "C65") (pin "2") (pinfunction "2_2") (pintype "passive"))
      (node (ref "C66") (pin "2") (pinfunction "2_2") (pintype "passive"))
      (node (ref "C67") (pin "2") (pinfunction "2_2") (pintype "passive"))
      (node (ref "C68") (pin "2") (pinfunction "2_2") (pintype "passive"))
      (node (ref "C69") (pin "2") (pinfunction "2_2") (pintype "passive"))
      (node (ref "D18") (pin "1") (pinfunction "CATHODE_1") (pintype "passive"))
      (node (ref "D20") (pin "1") (pinfunction "CATHODE_1") (pintype "passive"))
      (node (ref "I1") (pin "1") (pinfunction "GND_1") (pintype "power_in"))
      (node (ref "I2") (pin "1") (pinfunction "GND_1") (pintype "power_in"))
      (node (ref "Q7") (pin "2") (pinfunction "S_2") (pintype "passive"))
      (node (ref "Q8") (pin "2") (pinfunction "S_2") (pintype "passive"))
      (node (ref "R25") (pin "2") (pinfunction "2_2") (pintype "passive"))
      (node (ref "R26") (pin "2") (pinfunction "2_2") (pintype "passive"))
      (node (ref "R28") (pin "2") (pinfunction "2_2") (pintype "passive"))
      (node (ref "R33") (pin "2") (pinfunction "2_2") (pintype "passive"))
      (node (ref "R34") (pin "2") (pinfunction "2_2") (pintype "passive"))
      (node (ref "R36") (pin "2") (pinfunction "2_2") (pintype "passive"))
      (node (ref "U7") (pin "11") (pinfunction "Thermal_Pad_11") (pintype "power_in"))
      (node (ref "U7") (pin "8") (pinfunction "GND_8") (pintype "power_in"))
      (node (ref "U8") (pin "11") (pinfunction "Thermal_Pad_11") (pintype "power_in"))
      (node (ref "U8") (pin "8") (pinfunction "GND_8") (pintype "power_in"))
    )
    (net (code "22") (name "Net-(7V_PGOOD-Pad1)") (class "Default")
      (node (ref "7V_PGOOD") (pin "1") (pinfunction "1_1") (pintype "passive"))
      (node (ref "R29") (pin "2") (pinfunction "2_2") (pintype "passive"))
    )
    (net (code "23") (name "Net-(12V_PGOOD-Pad1)") (class "Default")
      (node (ref "12V_PGOOD") (pin "1") (pinfunction "1_1") (pintype "passive"))
      (node (ref "R21") (pin "2") (pinfunction "2_2") (pintype "passive"))
    )
    (net (code "24") (name "Net-(C43-Pad1)") (class "Default")
      (node (ref "C43") (pin "1") (pinfunction "1_1") (pintype "passive"))
      (node (ref "R27") (pin "2") (pinfunction "2_2") (pintype "passive"))
    )
    (net (code "25") (name "Net-(C69-Pad1)") (class "Default")
      (node (ref "C69") (pin "1") (pinfunction "1_1") (pintype "passive"))
      (node (ref "R35") (pin "1") (pinfunction "1_1") (pintype "passive"))
    )
    (net (code "26") (name "Net-(Q7-D)") (class "Default")
      (node (ref "12V_PGOOD") (pin "2") (pinfunction "2_2") (pintype "passive"))
      (node (ref "Q7") (pin "3") (pinfunction "D_3") (pintype "passive"))
    )
    (net (code "27") (name "Net-(Q8-D)") (class "Default")
      (node (ref "7V_PGOOD") (pin "2") (pinfunction "2_2") (pintype "passive"))
      (node (ref "Q8") (pin "3") (pinfunction "D_3") (pintype "passive"))
    )
    (net (code "29") (name "VBAT_Fused") (class "Default")
      (node (ref "C31") (pin "1") (pinfunction "1_1") (pintype "passive"))
      (node (ref "C32") (pin "1") (pinfunction "1_1") (pintype "passive"))
      (node (ref "R23") (pin "1") (pinfunction "1_1") (pintype "passive"))
      (node (ref "U7") (pin "2") (pinfunction "VIN_2") (pintype "input"))
      (node (ref "VBAT_FUSED") (pin "1") (pinfunction "0_1") (pintype "passive"))
    )
    (net (code "30") (name "VBAT_LDOS") (class "Default")
      (node (ref "C57") (pin "1") (pinfunction "1_1") (pintype "passive"))
      (node (ref "C58") (pin "1") (pinfunction "1_1") (pintype "passive"))
      (node (ref "R31") (pin "1") (pinfunction "1_1") (pintype "passive"))
      (node (ref "U8") (pin "2") (pinfunction "VIN_2") (pintype "input"))
      (node (ref "VBAT_LDOS") (pin "1") (pinfunction "0_1") (pintype "passive"))
    )
  )
)
